# Charger_USB.net
KiCad netlist of a schematic drawn in Altium Designer
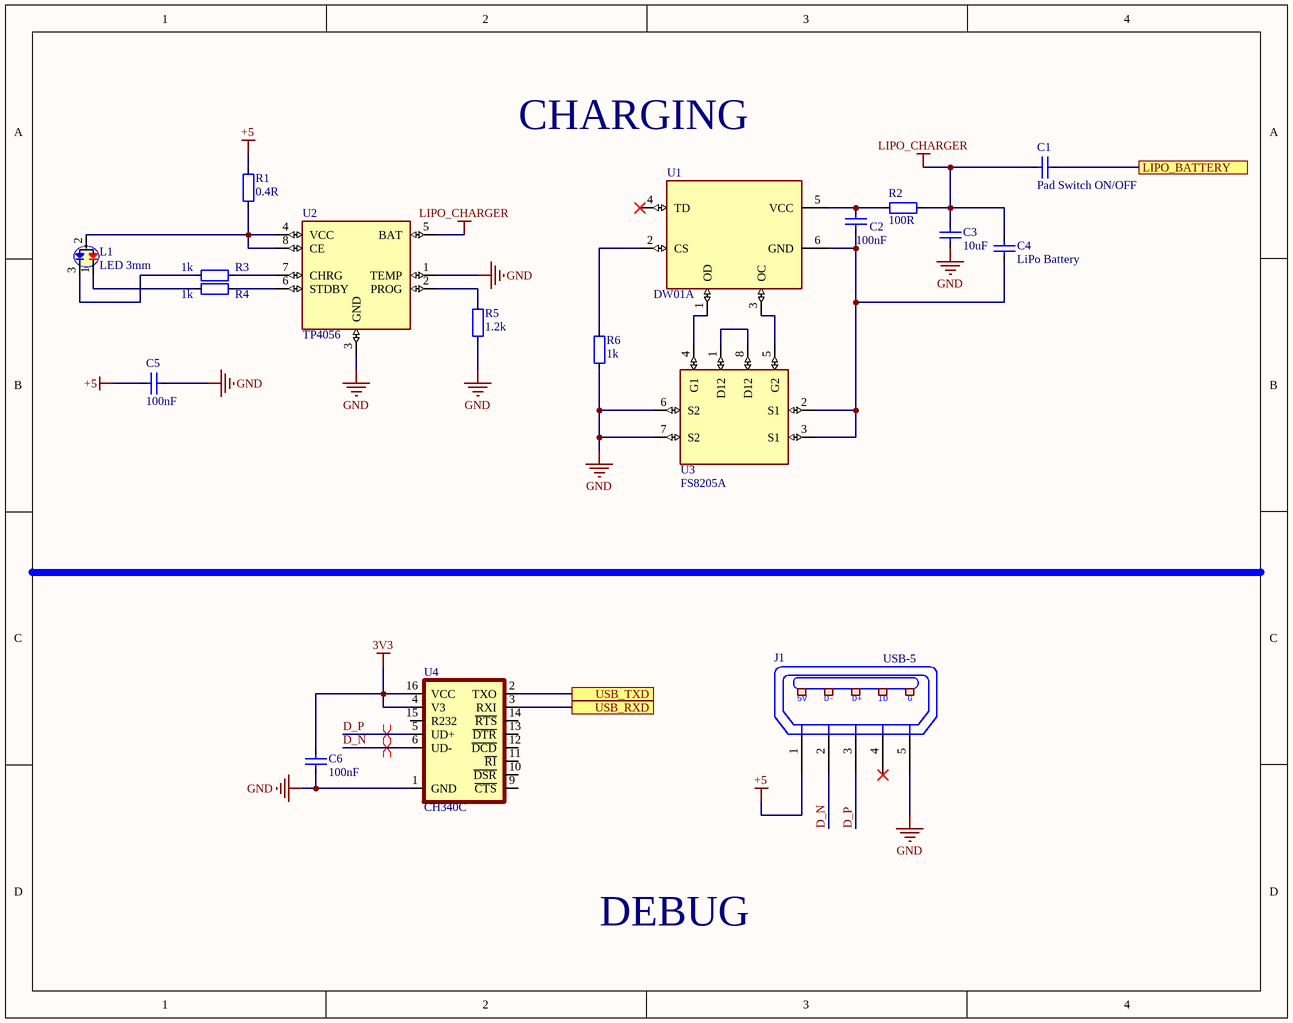
[diagram p0: Charger_USB.SchDoc]

(export (version "E")
  (design (tool "Eeschema 10.0.6"))
  (components
    (comp (ref "C1")
      (value "Pad Switch ON/OFF")
      (footprint "CAP_3216")
      (description "Capacitor")
      (fields (field (name "PUBLISHER") "Altium Limited"))
      (libsource (lib "My Library") (part "CapSMD"))
    )
    (comp (ref "C2")
      (value "100nF")
      (footprint "CAP_0805")
      (description "Capacitor")
      (fields (field (name "PUBLISHER") "Altium Limited"))
      (libsource (lib "My Library") (part "CapSMD"))
    )
    (comp (ref "C3")
      (value "10uF")
      (footprint "CAP_0805")
      (description "Capacitor")
      (fields (field (name "PUBLISHER") "Altium Limited"))
      (libsource (lib "My Library") (part "CapSMD"))
    )
    (comp (ref "C4")
      (value "LiPo Battery")
      (footprint "CAP_0805")
      (description "Capacitor")
      (fields (field (name "PUBLISHER") "Altium Limited"))
      (libsource (lib "My Library") (part "CapSMD"))
    )
    (comp (ref "C5")
      (value "100nF")
      (footprint "CAP_0805")
      (description "Capacitor")
      (fields (field (name "PUBLISHER") "Altium Limited"))
      (libsource (lib "My Library") (part "CapSMD"))
    )
    (comp (ref "C6")
      (value "100nF")
      (footprint "CAP_0805")
      (description "Capacitor")
      (fields (field (name "PUBLISHER") "Altium Limited"))
      (libsource (lib "My Library") (part "CapSMD"))
    )
    (comp (ref "J1")
      (value "USB-5")
      (footprint "USB-M1")
      (fields
        (field (name "MANUFACTURER") "FCI")
        (field (name "MANUFACTURER PART NUMBER") "10118193-0001LF")
        (field (name ".CREATOR") "MM")
        (field (name ".CHECKED PCB") "RF")
        (field (name ".CHECKED SCH") "MM")
      )
      (libsource (lib "My Library") (part "USB-5"))
    )
    (comp (ref "L1")
      (value "LED 3mm")
      (footprint "LED-3MM 2 MAU")
      (description "Cắm")
      (libsource (lib "Altium_Lib_by_KhueNguyenCreator") (part "LED 3m 2 mau Anot chung"))
    )
    (comp (ref "R1")
      (value "0.4R")
      (footprint "RES-SMD-0805")
      (description "Resistor")
      (fields
        (field (name "MANUFACTURER") "Generic Components")
        (field (name "PUBLISHER") "Altium Hobart Technology Centre")
      )
      (libsource (lib "My Library") (part "Resistor - SMD"))
    )
    (comp (ref "R2")
      (value "100R")
      (footprint "RES-SMD-0805")
      (description "Resistor")
      (fields
        (field (name "MANUFACTURER") "Generic Components")
        (field (name "PUBLISHER") "Altium Hobart Technology Centre")
      )
      (libsource (lib "My Library") (part "Resistor - SMD"))
    )
    (comp (ref "R3")
      (value "1k")
      (footprint "RES-SMD-0805")
      (description "Resistor")
      (fields
        (field (name "MANUFACTURER") "Generic Components")
        (field (name "PUBLISHER") "Altium Hobart Technology Centre")
      )
      (libsource (lib "My Library") (part "Resistor - SMD"))
    )
    (comp (ref "R4")
      (value "1k")
      (footprint "RES-SMD-0805")
      (description "Resistor")
      (fields
        (field (name "MANUFACTURER") "Generic Components")
        (field (name "PUBLISHER") "Altium Hobart Technology Centre")
      )
      (libsource (lib "My Library") (part "Resistor - SMD"))
    )
    (comp (ref "R5")
      (value "1.2k")
      (footprint "RES-SMD-0805")
      (description "Resistor")
      (fields
        (field (name "MANUFACTURER") "Generic Components")
        (field (name "PUBLISHER") "Altium Hobart Technology Centre")
      )
      (libsource (lib "My Library") (part "Resistor - SMD"))
    )
    (comp (ref "R6")
      (value "1k")
      (footprint "RES-SMD-0805")
      (description "Resistor")
      (fields
        (field (name "MANUFACTURER") "Generic Components")
        (field (name "PUBLISHER") "Altium Hobart Technology Centre")
      )
      (libsource (lib "My Library") (part "Resistor - SMD"))
    )
    (comp (ref "U1")
      (value "DW01A")
      (footprint "SOT23-6")
      (description "One Cell Lithium-ion/Polymer Battery Protection IC")
      (libsource (lib "My Library") (part "DW01A"))
    )
    (comp (ref "U2")
      (value "TP4056")
      (footprint "TP4056")
      (description "Complete single cell Li-Ion battery with a constant current / constant voltage linear charger")
      (libsource (lib "My Library") (part "TP4056"))
    )
    (comp (ref "U3") (value "FS8205A") (footprint "FS8205A") (libsource (lib "My Library") (part "FS8205A")))
    (comp (ref "U4")
      (value "CH340C")
      (footprint "SO016")
      (description "USB to serial chip CH340")
      (fields (field (name "MF") "WCH"))
      (libsource (lib "My Library") (part "CH340C"))
    )
  )
  (nets
    (net (code "1") (name "+5") (class "Default")
      (node (ref "C5") (pin "2") (pinfunction "2_2") (pintype "passive"))
      (node (ref "J1") (pin "1") (pinfunction "P1_1") (pintype "passive"))
      (node (ref "R1") (pin "1") (pinfunction "1_1") (pintype "passive"))
    )
    (net (code "2") (name "/D_N") (class "Default")
      (node (ref "J1") (pin "2") (pinfunction "P2_2") (pintype "passive"))
      (node (ref "U4") (pin "6") (pinfunction "UD-_6") (pintype "bidirectional"))
    )
    (net (code "3") (name "/D_P") (class "Default")
      (node (ref "J1") (pin "3") (pinfunction "P3_3") (pintype "passive"))
      (node (ref "U4") (pin "5") (pinfunction "UD+_5") (pintype "bidirectional"))
    )
    (net (code "4") (name "/LIPO_BATTERY") (class "Default")
      (node (ref "C1") (pin "2") (pinfunction "2_2") (pintype "passive"))
    )
    (net (code "5") (name "/USB_RXD") (class "Default")
      (node (ref "U4") (pin "3") (pinfunction "RXI_3") (pintype "bidirectional"))
    )
    (net (code "6") (name "/USB_TXD") (class "Default")
      (node (ref "U4") (pin "2") (pinfunction "TXO_2") (pintype "bidirectional"))
    )
    (net (code "7") (name "3V3") (class "Default")
      (node (ref "C6") (pin "2") (pinfunction "2_2") (pintype "passive"))
      (node (ref "U4") (pin "16") (pinfunction "VCC_16") (pintype "bidirectional"))
      (node (ref "U4") (pin "4") (pinfunction "V3_4") (pintype "bidirectional"))
    )
    (net (code "8") (name "GND") (class "Default")
      (node (ref "C3") (pin "2") (pinfunction "2_2") (pintype "passive"))
      (node (ref "C5") (pin "1") (pinfunction "1_1") (pintype "passive"))
      (node (ref "C6") (pin "1") (pinfunction "1_1") (pintype "passive"))
      (node (ref "J1") (pin "5") (pinfunction "P5_5") (pintype "passive"))
      (node (ref "R5") (pin "1") (pinfunction "1_1") (pintype "passive"))
      (node (ref "R6") (pin "1") (pinfunction "1_1") (pintype "passive"))
      (node (ref "U2") (pin "1") (pinfunction "TEMP_1") (pintype "bidirectional"))
      (node (ref "U2") (pin "3") (pinfunction "GND_3") (pintype "bidirectional"))
      (node (ref "U3") (pin "6") (pinfunction "S2_6") (pintype "bidirectional"))
      (node (ref "U3") (pin "7") (pinfunction "S2_7") (pintype "bidirectional"))
      (node (ref "U4") (pin "1") (pinfunction "GND_1") (pintype "bidirectional"))
    )
    (net (code "9") (name "LIPO_CHARGER") (class "Default")
      (node (ref "C1") (pin "1") (pinfunction "1_1") (pintype "passive"))
      (node (ref "C3") (pin "1") (pinfunction "1_1") (pintype "passive"))
      (node (ref "C4") (pin "1") (pinfunction "1_1") (pintype "passive"))
      (node (ref "R2") (pin "2") (pinfunction "2_2") (pintype "passive"))
      (node (ref "U2") (pin "5") (pinfunction "BAT_5") (pintype "bidirectional"))
    )
    (net (code "10") (name "Net-(L1-ANOT)") (class "Default")
      (node (ref "L1") (pin "2") (pinfunction "ANOT_2") (pintype "passive"))
      (node (ref "R1") (pin "2") (pinfunction "2_2") (pintype "passive"))
      (node (ref "U2") (pin "4") (pinfunction "VCC_4") (pintype "bidirectional"))
      (node (ref "U2") (pin "8") (pinfunction "CE_8") (pintype "bidirectional"))
    )
    (net (code "11") (name "Net-(L1-Katot_1)") (class "Default")
      (node (ref "L1") (pin "3") (pinfunction "Katot_1_3") (pintype "passive"))
      (node (ref "R3") (pin "2") (pinfunction "2_2") (pintype "passive"))
    )
    (net (code "12") (name "Net-(L1-Katot_2)") (class "Default")
      (node (ref "L1") (pin "1") (pinfunction "Katot_2_1") (pintype "passive"))
      (node (ref "R4") (pin "2") (pinfunction "2_2") (pintype "passive"))
    )
    (net (code "13") (name "Net-(U1-CS)") (class "Default")
      (node (ref "R6") (pin "2") (pinfunction "2_2") (pintype "passive"))
      (node (ref "U1") (pin "2") (pinfunction "CS_2") (pintype "bidirectional"))
    )
    (net (code "14") (name "Net-(U1-GND)") (class "Default")
      (node (ref "C2") (pin "2") (pinfunction "2_2") (pintype "passive"))
      (node (ref "C4") (pin "2") (pinfunction "2_2") (pintype "passive"))
      (node (ref "U1") (pin "6") (pinfunction "GND_6") (pintype "power_in"))
      (node (ref "U3") (pin "2") (pinfunction "S1_2") (pintype "bidirectional"))
      (node (ref "U3") (pin "3") (pinfunction "S1_3") (pintype "bidirectional"))
    )
    (net (code "15") (name "Net-(U1-OC)") (class "Default")
      (node (ref "U1") (pin "3") (pinfunction "OC_3") (pintype "bidirectional"))
      (node (ref "U3") (pin "5") (pinfunction "G2_5") (pintype "bidirectional"))
    )
    (net (code "16") (name "Net-(U1-OD)") (class "Default")
      (node (ref "U1") (pin "1") (pinfunction "OD_1") (pintype "bidirectional"))
      (node (ref "U3") (pin "4") (pinfunction "G1_4") (pintype "bidirectional"))
    )
    (net (code "17") (name "Net-(U1-VCC)") (class "Default")
      (node (ref "C2") (pin "1") (pinfunction "1_1") (pintype "passive"))
      (node (ref "R2") (pin "1") (pinfunction "1_1") (pintype "passive"))
      (node (ref "U1") (pin "5") (pinfunction "VCC_5") (pintype "power_in"))
    )
    (net (code "18") (name "Net-(U2-CHRG)") (class "Default")
      (node (ref "R3") (pin "1") (pinfunction "1_1") (pintype "passive"))
      (node (ref "U2") (pin "7") (pinfunction "CHRG_7") (pintype "bidirectional"))
    )
    (net (code "19") (name "Net-(U2-PROG)") (class "Default")
      (node (ref "R5") (pin "2") (pinfunction "2_2") (pintype "passive"))
      (node (ref "U2") (pin "2") (pinfunction "PROG_2") (pintype "bidirectional"))
    )
    (net (code "20") (name "Net-(U2-STDBY)") (class "Default")
      (node (ref "R4") (pin "1") (pinfunction "1_1") (pintype "passive"))
      (node (ref "U2") (pin "6") (pinfunction "STDBY_6") (pintype "bidirectional"))
    )
    (net (code "21") (name "Net-(U3-D12-Pad1)") (class "Default")
      (node (ref "U3") (pin "1") (pinfunction "D12_1") (pintype "bidirectional"))
      (node (ref "U3") (pin "8") (pinfunction "D12_8") (pintype "bidirectional"))
    )
    (net (code "22") (name "unconnected-(J1-P4-Pad4)") (class "Default")
      (node (ref "J1") (pin "4") (pinfunction "P4_4") (pintype "passive+no_connect"))
    )
    (net (code "23") (name "unconnected-(U1-TD-Pad4)") (class "Default")
      (node (ref "U1") (pin "4") (pinfunction "TD_4") (pintype "bidirectional+no_connect"))
    )
    (net (code "24") (name "unconnected-(U4-R232-Pad15)") (class "Default")
      (node (ref "U4") (pin "15") (pinfunction "R232_15") (pintype "bidirectional"))
    )
    (net (code "25") (name "unconnected-(U4-~{CTS}-Pad9)") (class "Default")
      (node (ref "U4") (pin "9") (pinfunction "~{CTS}_9") (pintype "bidirectional"))
    )
    (net (code "26") (name "unconnected-(U4-~{DCD}-Pad12)") (class "Default")
      (node (ref "U4") (pin "12") (pinfunction "~{DCD}_12") (pintype "bidirectional"))
    )
    (net (code "27") (name "unconnected-(U4-~{DSR}-Pad10)") (class "Default")
      (node (ref "U4") (pin "10") (pinfunction "~{DSR}_10") (pintype "bidirectional"))
    )
    (net (code "28") (name "unconnected-(U4-~{DTR}-Pad13)") (class "Default")
      (node (ref "U4") (pin "13") (pinfunction "~{DTR}_13") (pintype "bidirectional"))
    )
    (net (code "29") (name "unconnected-(U4-~{RI}-Pad11)") (class "Default")
      (node (ref "U4") (pin "11") (pinfunction "~{RI}_11") (pintype "bidirectional"))
    )
    (net (code "30") (name "unconnected-(U4-~{RTS}-Pad14)") (class "Default")
      (node (ref "U4") (pin "14") (pinfunction "~{RTS}_14") (pintype "bidirectional"))
    )
  )
)
